# OpenPack_BATMOD_V2p0_BAT.net
KiCad netlist of a schematic drawn in Altium Designer
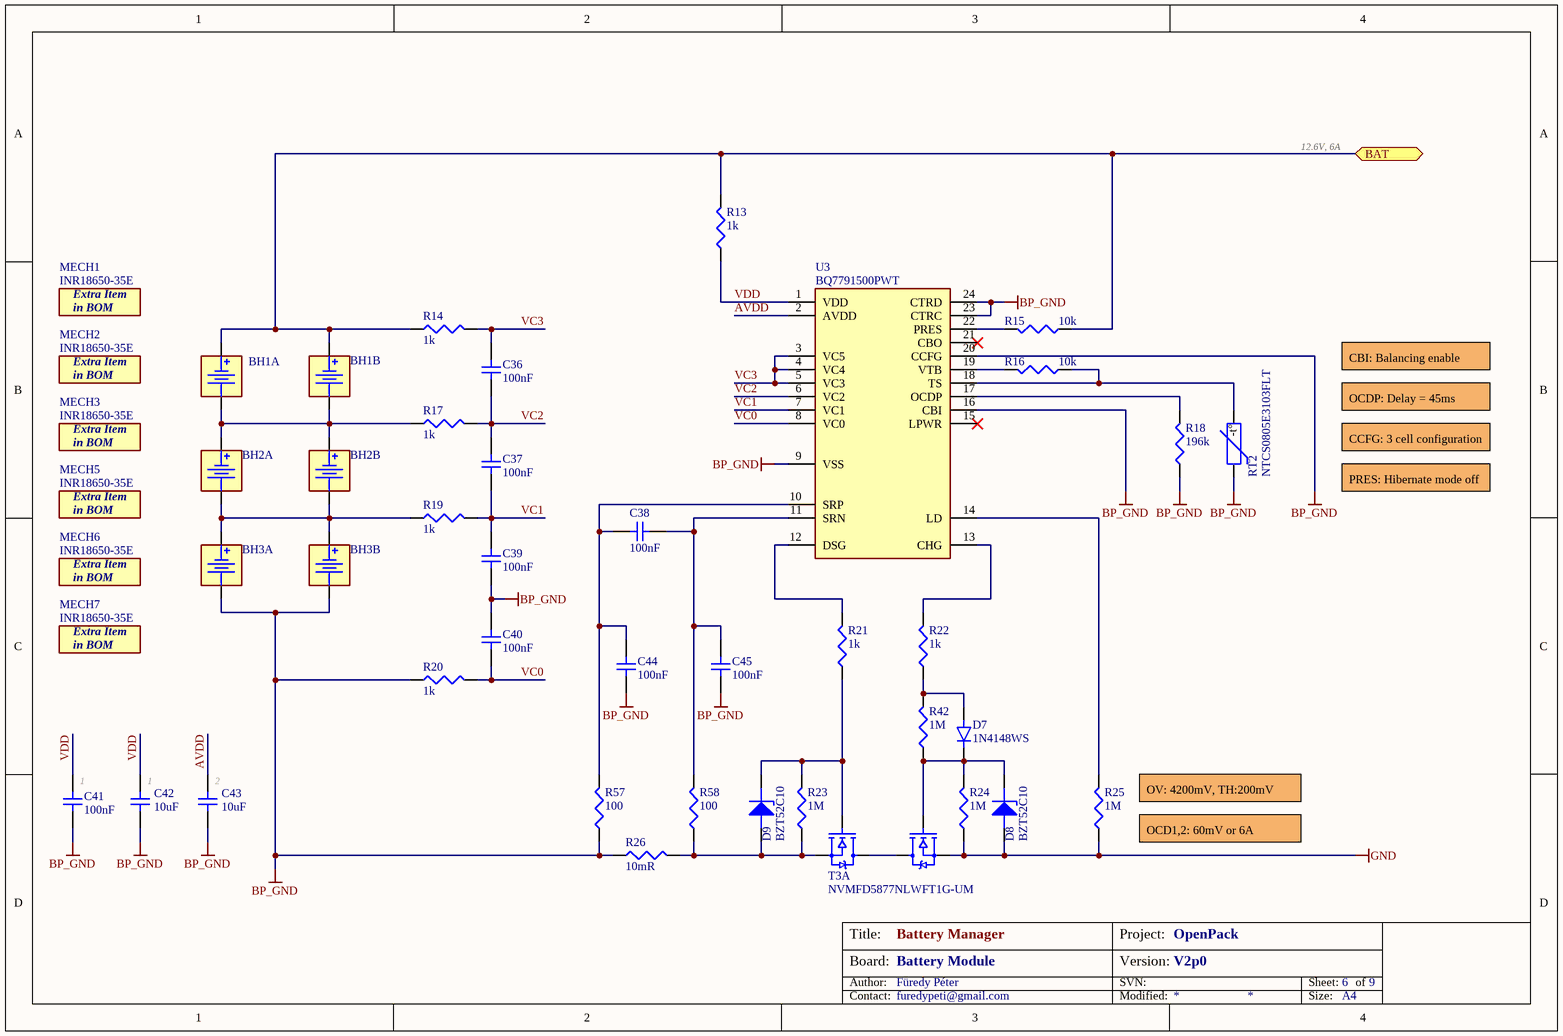
[diagram p0: OpenPack_BATMOD_V2p0_BAT.SchDoc]

(export (version "E")
  (design (tool "Eeschema 10.0.6"))
  (components
    (comp (ref "BH1")
      (value "12BHC186P-GR")
      (footprint "12BHC186P-GR")
      (description "Battery holder, 2x18650")
      (libsource (lib "SCHLIB") (part "12BHC186P-GR"))
    )
    (comp (ref "BH2")
      (value "12BHC186P-GR")
      (footprint "12BHC186P-GR")
      (description "Battery holder, 2x18650")
      (libsource (lib "SCHLIB") (part "12BHC186P-GR"))
    )
    (comp (ref "BH3")
      (value "12BHC186P-GR")
      (footprint "12BHC186P-GR")
      (description "Battery holder, 2x18650")
      (libsource (lib "SCHLIB") (part "12BHC186P-GR"))
    )
    (comp (ref "C36")
      (value "100nF")
      (footprint "CAP_0603")
      (description "MLCC capacitor")
      (libsource (lib "SCHLIB") (part "NP-CAPACITOR"))
    )
    (comp (ref "C37")
      (value "100nF")
      (footprint "CAP_0603")
      (description "MLCC capacitor")
      (libsource (lib "SCHLIB") (part "NP-CAPACITOR"))
    )
    (comp (ref "C38")
      (value "100nF")
      (footprint "CAP_0603")
      (description "MLCC capacitor")
      (libsource (lib "SCHLIB") (part "NP-CAPACITOR"))
    )
    (comp (ref "C39")
      (value "100nF")
      (footprint "CAP_0603")
      (description "MLCC capacitor")
      (libsource (lib "SCHLIB") (part "NP-CAPACITOR"))
    )
    (comp (ref "C40")
      (value "100nF")
      (footprint "CAP_0603")
      (description "MLCC capacitor")
      (libsource (lib "SCHLIB") (part "NP-CAPACITOR"))
    )
    (comp (ref "C41")
      (value "100nF")
      (footprint "CAP_0603")
      (description "MLCC capacitor")
      (libsource (lib "SCHLIB") (part "NP-CAPACITOR"))
    )
    (comp (ref "C42")
      (value "10uF")
      (footprint "CAP_1210")
      (description "UMK325BJ106KM-P")
      (fields (field (name "PART NUMBER") "810-CGA6P1X7R1N106K2"))
      (libsource (lib "SCHLIB") (part "NP-CAPACITOR"))
    )
    (comp (ref "C43")
      (value "10uF")
      (footprint "CAP_1210")
      (description "UMK325BJ106KM-P")
      (fields (field (name "PART NUMBER") "810-CGA6P1X7R1N106K2"))
      (libsource (lib "SCHLIB") (part "NP-CAPACITOR"))
    )
    (comp (ref "C44")
      (value "100nF")
      (footprint "CAP_0603")
      (description "MLCC capacitor")
      (libsource (lib "SCHLIB") (part "NP-CAPACITOR"))
    )
    (comp (ref "C45")
      (value "100nF")
      (footprint "CAP_0603")
      (description "MLCC capacitor")
      (libsource (lib "SCHLIB") (part "NP-CAPACITOR"))
    )
    (comp (ref "D7")
      (value "1N4148WS")
      (footprint "SOD-323")
      (description "Small Signal Diode, 75V, 150mA")
      (fields (field (name "PART NUMBER") "2453269"))
      (libsource (lib "SCHLIB") (part "1N4148WS"))
    )
    (comp (ref "D8")
      (value "BZT52C10")
      (footprint "SOD-123F")
      (description "Zener diode 10V 0.5W")
      (fields (field (name "PART NUMBER") "100.399.09"))
      (libsource (lib "SCHLIB") (part "BZT52C10"))
    )
    (comp (ref "D9")
      (value "BZT52C10")
      (footprint "SOD-123F")
      (description "Zener diode 10V 0.5W")
      (fields (field (name "PART NUMBER") "100.399.09"))
      (libsource (lib "SCHLIB") (part "BZT52C10"))
    )
    (comp (ref "MECH1")
      (value "INR18650-35E")
      (description "Li-Ion Battery cell, 18650, 3.7V, 3400mAh")
      (fields (field (name "PART NUMBER") "100.496.87"))
      (libsource (lib "SCHLIB") (part "INR18650-35E"))
    )
    (comp (ref "MECH2")
      (value "INR18650-35E")
      (description "Li-Ion Battery cell, 18650, 3.7V, 3400mAh")
      (fields (field (name "PART NUMBER") "100.496.87"))
      (libsource (lib "SCHLIB") (part "INR18650-35E"))
    )
    (comp (ref "MECH3")
      (value "INR18650-35E")
      (description "Li-Ion Battery cell, 18650, 3.7V, 3400mAh")
      (fields (field (name "PART NUMBER") "100.496.87"))
      (libsource (lib "SCHLIB") (part "INR18650-35E"))
    )
    (comp (ref "MECH5")
      (value "INR18650-35E")
      (description "Li-Ion Battery cell, 18650, 3.7V, 3400mAh")
      (fields (field (name "PART NUMBER") "100.496.87"))
      (libsource (lib "SCHLIB") (part "INR18650-35E"))
    )
    (comp (ref "MECH6")
      (value "INR18650-35E")
      (description "Li-Ion Battery cell, 18650, 3.7V, 3400mAh")
      (fields (field (name "PART NUMBER") "100.496.87"))
      (libsource (lib "SCHLIB") (part "INR18650-35E"))
    )
    (comp (ref "MECH7")
      (value "INR18650-35E")
      (description "Li-Ion Battery cell, 18650, 3.7V, 3400mAh")
      (fields (field (name "PART NUMBER") "100.496.87"))
      (libsource (lib "SCHLIB") (part "INR18650-35E"))
    )
    (comp (ref "R13")
      (value "1k")
      (footprint "RES-0603")
      (description "Metal Film Resistor")
      (libsource (lib "SCHLIB") (part "RESISTOR"))
    )
    (comp (ref "R14")
      (value "1k")
      (footprint "RES-0603")
      (description "Metal Film Resistor")
      (libsource (lib "SCHLIB") (part "RESISTOR"))
    )
    (comp (ref "R15")
      (value "10k")
      (footprint "RES-0603")
      (description "Metal Film Resistor")
      (libsource (lib "SCHLIB") (part "RESISTOR"))
    )
    (comp (ref "R16")
      (value "10k")
      (footprint "RES-0603")
      (description "Metal Film Resistor")
      (libsource (lib "SCHLIB") (part "RESISTOR"))
    )
    (comp (ref "R17")
      (value "1k")
      (footprint "RES-0603")
      (description "Metal Film Resistor")
      (libsource (lib "SCHLIB") (part "RESISTOR"))
    )
    (comp (ref "R18")
      (value "196k")
      (footprint "RES-0603")
      (description "Metal Film Resistor")
      (libsource (lib "SCHLIB") (part "RESISTOR"))
    )
    (comp (ref "R19")
      (value "1k")
      (footprint "RES-0603")
      (description "Metal Film Resistor")
      (libsource (lib "SCHLIB") (part "RESISTOR"))
    )
    (comp (ref "R20")
      (value "1k")
      (footprint "RES-0603")
      (description "Metal Film Resistor")
      (libsource (lib "SCHLIB") (part "RESISTOR"))
    )
    (comp (ref "R21")
      (value "1k")
      (footprint "RES-0603")
      (description "Metal Film Resistor")
      (libsource (lib "SCHLIB") (part "RESISTOR"))
    )
    (comp (ref "R22")
      (value "1k")
      (footprint "RES-0603")
      (description "Metal Film Resistor")
      (libsource (lib "SCHLIB") (part "RESISTOR"))
    )
    (comp (ref "R23")
      (value "1M")
      (footprint "RES-0603")
      (description "Metal Film Resistor")
      (libsource (lib "SCHLIB") (part "RESISTOR"))
    )
    (comp (ref "R24")
      (value "1M")
      (footprint "RES-0603")
      (description "Metal Film Resistor")
      (libsource (lib "SCHLIB") (part "RESISTOR"))
    )
    (comp (ref "R25")
      (value "1M")
      (footprint "RES-0603")
      (description "Metal Film Resistor")
      (libsource (lib "SCHLIB") (part "RESISTOR"))
    )
    (comp (ref "R26")
      (value "10mR")
      (footprint "RES-2512")
      (description "Metal Film Resistor")
      (libsource (lib "SCHLIB") (part "RESISTOR"))
    )
    (comp (ref "R42")
      (value "1M")
      (footprint "RES-0603")
      (description "Metal Film Resistor")
      (libsource (lib "SCHLIB") (part "RESISTOR"))
    )
    (comp (ref "R57")
      (value "100")
      (footprint "RES-0603")
      (description "Metal Film Resistor")
      (libsource (lib "SCHLIB") (part "RESISTOR"))
    )
    (comp (ref "R58")
      (value "100")
      (footprint "RES-0603")
      (description "Metal Film Resistor")
      (libsource (lib "SCHLIB") (part "RESISTOR"))
    )
    (comp (ref "RT2")
      (value "NTCS0805E3103FLT")
      (footprint "RES-0805")
      (description "NTC (Negative Temperature Coefficient) Thermistors 10Kohms 1%")
      (fields (field (name "PART NUMBER") "594-NTCS0805E3103FLT"))
      (libsource (lib "SCHLIB") (part "NTCS0805E3103FLT"))
    )
    (comp (ref "T3")
      (value "NVMFD5877NLWFT1G-UM")
      (footprint "SO-8FL (DFN8)")
      (description "Power NMOSFET Dual, 60V, 17A, 36mΩ")
      (fields (field (name "PART NUMBER") "863-FD5877NLWFT1G-UM"))
      (libsource (lib "SCHLIB") (part "NVMFD5877NLWFT1G-UM"))
    )
    (comp (ref "U3")
      (value "BQ7791500PWT")
      (footprint "TSSOP24")
      (description "Battery Management 3-series to 5-series stackable")
      (fields (field (name "PART NUMBER") "595-BQ7791500PWR"))
      (libsource (lib "SCHLIB") (part "BQ7791500PWT"))
    )
  )
  (nets
    (net (code "1") (name "/AVDD") (class "Default")
      (node (ref "C43") (pin "2") (pinfunction "2_2") (pintype "passive"))
      (node (ref "U3") (pin "2") (pinfunction "AVDD_2") (pintype "passive"))
    )
    (net (code "2") (name "/BAT") (class "Default")
      (node (ref "BH1") (pin "2") (pinfunction "2_2") (pintype "passive"))
      (node (ref "BH1") (pin "4") (pinfunction "4_4") (pintype "passive"))
      (node (ref "R13") (pin "2") (pintype "passive"))
      (node (ref "R14") (pin "1") (pintype "passive"))
      (node (ref "R15") (pin "1") (pintype "passive"))
    )
    (net (code "3") (name "/VC0") (class "Default")
      (node (ref "C40") (pin "1") (pinfunction "1_1") (pintype "passive"))
      (node (ref "R20") (pin "2") (pintype "passive"))
      (node (ref "U3") (pin "8") (pinfunction "VC0_8") (pintype "passive"))
    )
    (net (code "4") (name "/VC1") (class "Default")
      (node (ref "C37") (pin "1") (pinfunction "1_1") (pintype "passive"))
      (node (ref "C39") (pin "2") (pinfunction "2_2") (pintype "passive"))
      (node (ref "R19") (pin "2") (pintype "passive"))
      (node (ref "U3") (pin "7") (pinfunction "VC1_7") (pintype "passive"))
    )
    (net (code "5") (name "/VC2") (class "Default")
      (node (ref "C36") (pin "1") (pinfunction "1_1") (pintype "passive"))
      (node (ref "C37") (pin "2") (pinfunction "2_2") (pintype "passive"))
      (node (ref "R17") (pin "2") (pintype "passive"))
      (node (ref "U3") (pin "6") (pinfunction "VC2_6") (pintype "passive"))
    )
    (net (code "6") (name "/VC3") (class "Default")
      (node (ref "C36") (pin "2") (pinfunction "2_2") (pintype "passive"))
      (node (ref "R14") (pin "2") (pintype "passive"))
      (node (ref "U3") (pin "3") (pinfunction "VC5_3") (pintype "passive"))
      (node (ref "U3") (pin "4") (pinfunction "VC4_4") (pintype "passive"))
      (node (ref "U3") (pin "5") (pinfunction "VC3_5") (pintype "passive"))
    )
    (net (code "7") (name "/VDD") (class "Default")
      (node (ref "C41") (pin "2") (pinfunction "2_2") (pintype "passive"))
      (node (ref "C42") (pin "2") (pinfunction "2_2") (pintype "passive"))
      (node (ref "R13") (pin "1") (pintype "passive"))
      (node (ref "U3") (pin "1") (pinfunction "VDD_1") (pintype "passive"))
    )
    (net (code "8") (name "BP_GND") (class "Default")
      (node (ref "BH3") (pin "1") (pinfunction "1_1") (pintype "passive"))
      (node (ref "BH3") (pin "3") (pinfunction "3_3") (pintype "passive"))
      (node (ref "C39") (pin "1") (pinfunction "1_1") (pintype "passive"))
      (node (ref "C40") (pin "2") (pinfunction "2_2") (pintype "passive"))
      (node (ref "C41") (pin "1") (pinfunction "1_1") (pintype "passive"))
      (node (ref "C42") (pin "1") (pinfunction "1_1") (pintype "passive"))
      (node (ref "C43") (pin "1") (pinfunction "1_1") (pintype "passive"))
      (node (ref "C44") (pin "1") (pinfunction "1_1") (pintype "passive"))
      (node (ref "C45") (pin "1") (pinfunction "1_1") (pintype "passive"))
      (node (ref "R18") (pin "1") (pintype "passive"))
      (node (ref "R20") (pin "1") (pintype "passive"))
      (node (ref "R26") (pin "1") (pintype "passive"))
      (node (ref "R57") (pin "1") (pintype "passive"))
      (node (ref "RT2") (pin "1") (pintype "passive"))
      (node (ref "U3") (pin "16") (pinfunction "CBI_16") (pintype "passive"))
      (node (ref "U3") (pin "20") (pinfunction "CCFG_20") (pintype "passive"))
      (node (ref "U3") (pin "23") (pinfunction "CTRC_23") (pintype "passive"))
      (node (ref "U3") (pin "24") (pinfunction "CTRD_24") (pintype "passive"))
      (node (ref "U3") (pin "9") (pinfunction "VSS_9") (pintype "passive"))
    )
    (net (code "9") (name "GND") (class "Default")
      (node (ref "D8") (pin "1") (pinfunction "A_1") (pintype "passive"))
      (node (ref "R24") (pin "1") (pintype "passive"))
      (node (ref "R25") (pin "1") (pintype "passive"))
      (node (ref "T3") (pin "3") (pinfunction "3_3") (pintype "passive"))
    )
    (net (code "10") (name "Net-(BH1-Pad1)") (class "Default")
      (node (ref "BH1") (pin "1") (pinfunction "1_1") (pintype "passive"))
      (node (ref "BH1") (pin "3") (pinfunction "3_3") (pintype "passive"))
      (node (ref "BH2") (pin "2") (pinfunction "2_2") (pintype "passive"))
      (node (ref "BH2") (pin "4") (pinfunction "4_4") (pintype "passive"))
      (node (ref "R17") (pin "1") (pintype "passive"))
    )
    (net (code "11") (name "Net-(BH2-Pad1)") (class "Default")
      (node (ref "BH2") (pin "1") (pinfunction "1_1") (pintype "passive"))
      (node (ref "BH2") (pin "3") (pinfunction "3_3") (pintype "passive"))
      (node (ref "BH3") (pin "2") (pinfunction "2_2") (pintype "passive"))
      (node (ref "BH3") (pin "4") (pinfunction "4_4") (pintype "passive"))
      (node (ref "R19") (pin "1") (pintype "passive"))
    )
    (net (code "12") (name "Net-(D7-Pad1)") (class "Default")
      (node (ref "D7") (pin "1") (pinfunction "1_1") (pintype "passive"))
      (node (ref "R22") (pin "1") (pintype "passive"))
      (node (ref "R42") (pin "2") (pintype "passive"))
    )
    (net (code "13") (name "Net-(D8-K)") (class "Default")
      (node (ref "D7") (pin "2") (pinfunction "2_2") (pintype "passive"))
      (node (ref "D8") (pin "2") (pinfunction "K_2") (pintype "passive"))
      (node (ref "R24") (pin "2") (pintype "passive"))
      (node (ref "R42") (pin "1") (pintype "passive"))
      (node (ref "T3") (pin "4") (pinfunction "4_4") (pintype "passive"))
    )
    (net (code "14") (name "Net-(D9-A)") (class "Default")
      (node (ref "D9") (pin "1") (pinfunction "A_1") (pintype "passive"))
      (node (ref "R23") (pin "1") (pintype "passive"))
      (node (ref "R26") (pin "2") (pintype "passive"))
      (node (ref "R58") (pin "1") (pintype "passive"))
      (node (ref "T3") (pin "1") (pinfunction "1_1") (pintype "passive"))
    )
    (net (code "15") (name "Net-(D9-K)") (class "Default")
      (node (ref "D9") (pin "2") (pinfunction "K_2") (pintype "passive"))
      (node (ref "R21") (pin "1") (pintype "passive"))
      (node (ref "R23") (pin "2") (pintype "passive"))
      (node (ref "T3") (pin "2") (pinfunction "2_2") (pintype "passive"))
    )
    (net (code "16") (name "Net-(T3-Pad10)") (class "Default")
      (node (ref "T3") (pin "10") (pinfunction "10_10") (pintype "passive"))
      (node (ref "T3") (pin "9") (pinfunction "9_9") (pintype "passive"))
    )
    (net (code "17") (name "Net-(U3-CHG)") (class "Default")
      (node (ref "R22") (pin "2") (pintype "passive"))
      (node (ref "U3") (pin "13") (pinfunction "CHG_13") (pintype "passive"))
    )
    (net (code "18") (name "Net-(U3-DSG)") (class "Default")
      (node (ref "R21") (pin "2") (pintype "passive"))
      (node (ref "U3") (pin "12") (pinfunction "DSG_12") (pintype "passive"))
    )
    (net (code "19") (name "Net-(U3-LD)") (class "Default")
      (node (ref "R25") (pin "2") (pintype "passive"))
      (node (ref "U3") (pin "14") (pinfunction "LD_14") (pintype "passive"))
    )
    (net (code "20") (name "Net-(U3-OCDP)") (class "Default")
      (node (ref "R18") (pin "2") (pintype "passive"))
      (node (ref "U3") (pin "17") (pinfunction "OCDP_17") (pintype "passive"))
    )
    (net (code "21") (name "Net-(U3-PRES)") (class "Default")
      (node (ref "R15") (pin "2") (pintype "passive"))
      (node (ref "U3") (pin "22") (pinfunction "PRES_22") (pintype "passive"))
    )
    (net (code "22") (name "Net-(U3-SRN)") (class "Default")
      (node (ref "C38") (pin "1") (pinfunction "1_1") (pintype "passive"))
      (node (ref "C45") (pin "2") (pinfunction "2_2") (pintype "passive"))
      (node (ref "R58") (pin "2") (pintype "passive"))
      (node (ref "U3") (pin "11") (pinfunction "SRN_11") (pintype "passive"))
    )
    (net (code "23") (name "Net-(U3-SRP)") (class "Default")
      (node (ref "C38") (pin "2") (pinfunction "2_2") (pintype "passive"))
      (node (ref "C44") (pin "2") (pinfunction "2_2") (pintype "passive"))
      (node (ref "R57") (pin "2") (pintype "passive"))
      (node (ref "U3") (pin "10") (pinfunction "SRP_10") (pintype "passive"))
    )
    (net (code "24") (name "Net-(U3-TS)") (class "Default")
      (node (ref "R16") (pin "1") (pintype "passive"))
      (node (ref "RT2") (pin "2") (pintype "passive"))
      (node (ref "U3") (pin "18") (pinfunction "TS_18") (pintype "passive"))
    )
    (net (code "25") (name "Net-(U3-VTB)") (class "Default")
      (node (ref "R16") (pin "2") (pintype "passive"))
      (node (ref "U3") (pin "19") (pinfunction "VTB_19") (pintype "passive"))
    )
    (net (code "26") (name "unconnected-(U3-CBO-Pad21)") (class "Default")
      (node (ref "U3") (pin "21") (pinfunction "CBO_21") (pintype "passive+no_connect"))
    )
    (net (code "27") (name "unconnected-(U3-LPWR-Pad15)") (class "Default")
      (node (ref "U3") (pin "15") (pinfunction "LPWR_15") (pintype "passive+no_connect"))
    )
  )
)
